# 2.net
KiCad netlist of a schematic drawn in Altium Designer
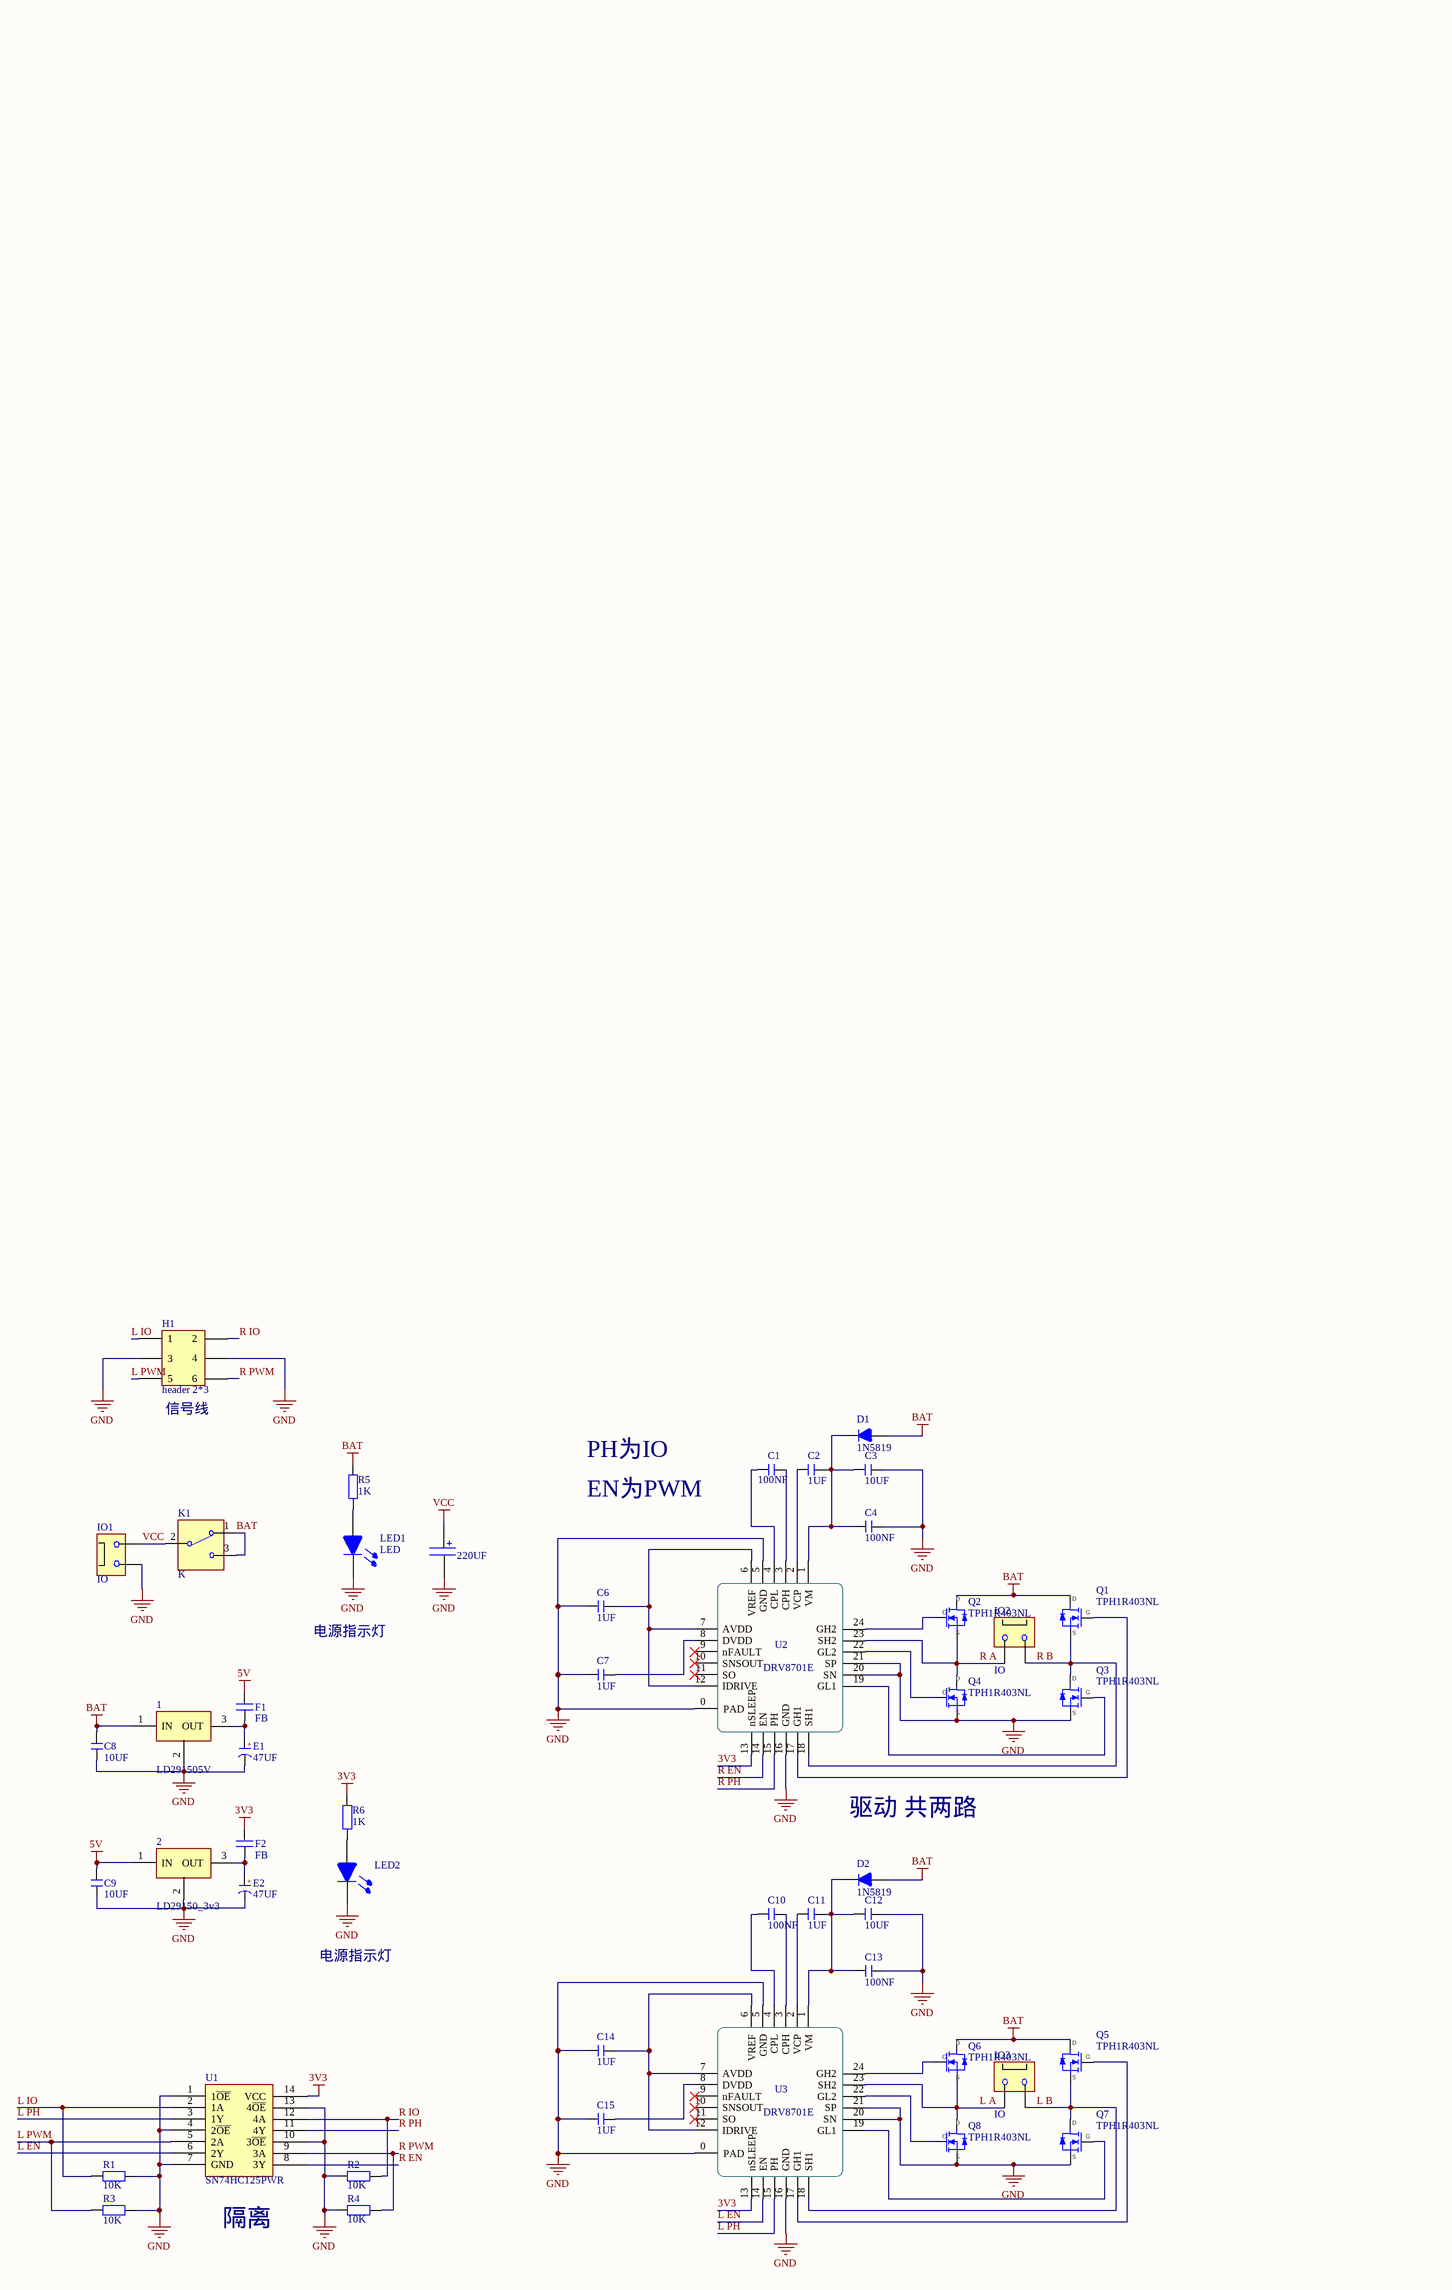
[diagram p0: 驱动2.SchDoc]

(export (version "E")
  (design (tool "Eeschema 10.0.6"))
  (components
    (comp (ref "1")
      (value "LD291505V")
      (footprint "LC-TO-252-2")
      (description "5v转压")
      (libsource (lib "驱动2") (part "LD291505V"))
    )
    (comp (ref "2")
      (value "LD29150_3v3")
      (footprint "LC-TO-252-2")
      (description "转压3v3")
      (libsource (lib "驱动2") (part "LD29150_3v3"))
    )
    (comp (ref "C1")
      (value "100NF")
      (footprint "0603-C")
      (description "无极性贴片电容")
      (fields (field (name "版权归属") "源创客"))
      (libsource (lib "驱动2") (part "C"))
    )
    (comp (ref "C2")
      (value "1UF")
      (footprint "0603-C")
      (description "无极性贴片电容")
      (fields (field (name "版权归属") "源创客"))
      (libsource (lib "驱动2") (part "C"))
    )
    (comp (ref "C3")
      (value "10UF")
      (footprint "0603-C")
      (description "无极性贴片电容")
      (fields (field (name "版权归属") "源创客"))
      (libsource (lib "驱动2") (part "C"))
    )
    (comp (ref "C4")
      (value "100NF")
      (footprint "0603-C")
      (description "无极性贴片电容")
      (fields (field (name "版权归属") "源创客"))
      (libsource (lib "驱动2") (part "C"))
    )
    (comp (ref "C5")
      (value "220UF")
      (footprint "Cap electro 6_3x12_5x2_5mm")
      (description "有极电容")
      (libsource (lib "驱动2") (part "C+"))
    )
    (comp (ref "C6")
      (value "1UF")
      (footprint "0603-C")
      (description "无极性贴片电容")
      (fields (field (name "版权归属") "源创客"))
      (libsource (lib "驱动2") (part "C"))
    )
    (comp (ref "C7")
      (value "1UF")
      (footprint "0603-C")
      (description "无极性贴片电容")
      (fields (field (name "版权归属") "源创客"))
      (libsource (lib "驱动2") (part "C"))
    )
    (comp (ref "C8")
      (value "10UF")
      (footprint "0603-C")
      (description "无极性贴片电容")
      (fields (field (name "版权归属") "源创客"))
      (libsource (lib "驱动2") (part "C"))
    )
    (comp (ref "C9")
      (value "10UF")
      (footprint "0603-C")
      (description "无极性贴片电容")
      (fields (field (name "版权归属") "源创客"))
      (libsource (lib "驱动2") (part "C"))
    )
    (comp (ref "C10")
      (value "100NF")
      (footprint "0603-C")
      (description "无极性贴片电容")
      (fields (field (name "版权归属") "源创客"))
      (libsource (lib "驱动2") (part "C"))
    )
    (comp (ref "C11")
      (value "1UF")
      (footprint "0603-C")
      (description "无极性贴片电容")
      (fields (field (name "版权归属") "源创客"))
      (libsource (lib "驱动2") (part "C"))
    )
    (comp (ref "C12")
      (value "10UF")
      (footprint "0603-C")
      (description "无极性贴片电容")
      (fields (field (name "版权归属") "源创客"))
      (libsource (lib "驱动2") (part "C"))
    )
    (comp (ref "C13")
      (value "100NF")
      (footprint "0603-C")
      (description "无极性贴片电容")
      (fields (field (name "版权归属") "源创客"))
      (libsource (lib "驱动2") (part "C"))
    )
    (comp (ref "C14")
      (value "1UF")
      (footprint "0603-C")
      (description "无极性贴片电容")
      (fields (field (name "版权归属") "源创客"))
      (libsource (lib "驱动2") (part "C"))
    )
    (comp (ref "C15")
      (value "1UF")
      (footprint "0603-C")
      (description "无极性贴片电容")
      (fields (field (name "版权归属") "源创客"))
      (libsource (lib "驱动2") (part "C"))
    )
    (comp (ref "D1")
      (value "1N5819")
      (footprint "SMA")
      (description "二极管")
      (libsource (lib "驱动2") (part "D"))
    )
    (comp (ref "D2")
      (value "1N5819")
      (footprint "SMA")
      (description "二极管")
      (libsource (lib "驱动2") (part "D"))
    )
    (comp (ref "E1")
      (value "47UF")
      (footprint "A106C钽电容")
      (description "贴片钽电容")
      (fields (field (name "版权归属") "源创客"))
      (libsource (lib "驱动2") (part "C-CD"))
    )
    (comp (ref "E2")
      (value "47UF")
      (footprint "A106C钽电容")
      (description "贴片钽电容")
      (fields (field (name "版权归属") "源创客"))
      (libsource (lib "驱动2") (part "C-CD"))
    )
    (comp (ref "F1")
      (value "FB")
      (footprint "0603-C")
      (description "0欧磁珠")
      (libsource (lib "驱动2") (part "FB"))
    )
    (comp (ref "F2")
      (value "FB")
      (footprint "0603-C")
      (description "0欧磁珠")
      (libsource (lib "驱动2") (part "FB"))
    )
    (comp (ref "H1")
      (value "header 2*3")
      (footprint "HDR2.54-LI-2x3P")
      (description "编码器，PWM")
      (libsource (lib "驱动2") (part "header 2*3"))
    )
    (comp (ref "IO1") (value "IO") (footprint "XT30") (description "接口") (libsource (lib "") (part "IO_1")))
    (comp (ref "IO2") (value "IO") (footprint "XT30") (description "接口") (libsource (lib "驱动2") (part "IO")))
    (comp (ref "IO3") (value "IO") (footprint "XT30") (description "接口") (libsource (lib "驱动2") (part "IO")))
    (comp (ref "K1")
      (value "K")
      (footprint "SW-SPDT-3A250V")
      (description "开关")
      (libsource (lib "驱动2") (part "K"))
    )
    (comp (ref "LED1") (value "LED") (footprint "0603-LED-R") (libsource (lib "驱动2") (part "LED")))
    (comp (ref "LED2") (value "LED") (footprint "0603-LED-R") (libsource (lib "驱动2") (part "LED")))
    (comp (ref "Q1")
      (value "TPH1R403NL")
      (footprint "DFN5x6")
      (description "东芝 N沟 MOS")
      (libsource (lib "逐飞集成封装库") (part "TPH1R403NL"))
    )
    (comp (ref "Q2")
      (value "TPH1R403NL")
      (footprint "DFN5x6")
      (description "东芝 N沟 MOS")
      (libsource (lib "逐飞集成封装库") (part "TPH1R403NL"))
    )
    (comp (ref "Q3")
      (value "TPH1R403NL")
      (footprint "DFN5x6")
      (description "东芝 N沟 MOS")
      (libsource (lib "逐飞集成封装库") (part "TPH1R403NL"))
    )
    (comp (ref "Q4")
      (value "TPH1R403NL")
      (footprint "DFN5x6")
      (description "东芝 N沟 MOS")
      (libsource (lib "逐飞集成封装库") (part "TPH1R403NL"))
    )
    (comp (ref "Q5")
      (value "TPH1R403NL")
      (footprint "DFN5x6")
      (description "东芝 N沟 MOS")
      (libsource (lib "逐飞集成封装库") (part "TPH1R403NL"))
    )
    (comp (ref "Q6")
      (value "TPH1R403NL")
      (footprint "DFN5x6")
      (description "东芝 N沟 MOS")
      (libsource (lib "逐飞集成封装库") (part "TPH1R403NL"))
    )
    (comp (ref "Q7")
      (value "TPH1R403NL")
      (footprint "DFN5x6")
      (description "东芝 N沟 MOS")
      (libsource (lib "逐飞集成封装库") (part "TPH1R403NL"))
    )
    (comp (ref "Q8")
      (value "TPH1R403NL")
      (footprint "DFN5x6")
      (description "东芝 N沟 MOS")
      (libsource (lib "逐飞集成封装库") (part "TPH1R403NL"))
    )
    (comp (ref "R1")
      (value "10K")
      (footprint "LC-0603_R")
      (description "1K")
      (fields (field (name "Comment") "Res2") (field (name "PUBLISHER") "Altium Limited"))
      (libsource (lib "") (part "Res2_3_2"))
    )
    (comp (ref "R2")
      (value "10K")
      (footprint "LC-0603_R")
      (description "1K")
      (fields (field (name "Comment") "Res2") (field (name "PUBLISHER") "Altium Limited"))
      (libsource (lib "") (part "Res2_3_1"))
    )
    (comp (ref "R3")
      (value "10K")
      (footprint "LC-0603_R")
      (description "1K")
      (fields (field (name "Comment") "Res2") (field (name "PUBLISHER") "Altium Limited"))
      (libsource (lib "") (part "Res2_3_1"))
    )
    (comp (ref "R4")
      (value "10K")
      (footprint "LC-0603_R")
      (description "1K")
      (fields (field (name "Comment") "Res2") (field (name "PUBLISHER") "Altium Limited"))
      (libsource (lib "") (part "Res2_3_1"))
    )
    (comp (ref "R5")
      (value "1K")
      (footprint "LC-0603_R")
      (fields (field (name "Comment") "Res2") (field (name "PUBLISHER") "Altium Limited"))
      (libsource (lib "驱动2") (part "Res2_3"))
    )
    (comp (ref "R6")
      (value "1K")
      (footprint "LC-0603_R")
      (fields (field (name "Comment") "Res2") (field (name "PUBLISHER") "Altium Limited"))
      (libsource (lib "驱动2") (part "Res2_3"))
    )
    (comp (ref "U1")
      (value "SN74HC125PWR")
      (footprint "TSSOP14")
      (fields (field (name "PUBLISHER") "Altium Limited"))
      (libsource (lib "驱动2") (part "SN74HC125PWR"))
    )
    (comp (ref "U2")
      (value "DRV8701E")
      (footprint "QFN24-4x4")
      (description "DRV8701E Ti全桥驱动芯片")
      (libsource (lib "逐飞集成封装库") (part "DRV8701E"))
    )
    (comp (ref "U3")
      (value "DRV8701E")
      (footprint "QFN24-4x4")
      (description "DRV8701E Ti全桥驱动芯片")
      (libsource (lib "逐飞集成封装库") (part "DRV8701E"))
    )
  )
  (nets
    (net (code "1") (name "/L A") (class "Default")
      (node (ref "IO3") (pin "2") (pinfunction "2_2") (pintype "passive"))
      (node (ref "Q6") (pin "3") (pinfunction "S_3") (pintype "passive"))
      (node (ref "Q8") (pin "1") (pinfunction "D_1") (pintype "passive"))
      (node (ref "U3") (pin "23") (pinfunction "SH2_23") (pintype "passive"))
    )
    (net (code "2") (name "/L B") (class "Default")
      (node (ref "IO3") (pin "1") (pinfunction "1_1") (pintype "passive"))
      (node (ref "Q5") (pin "3") (pinfunction "S_3") (pintype "passive"))
      (node (ref "Q7") (pin "1") (pinfunction "D_1") (pintype "passive"))
      (node (ref "U3") (pin "18") (pinfunction "SH1_18") (pintype "passive"))
    )
    (net (code "3") (name "/L EN") (class "Default")
      (node (ref "U1") (pin "6") (pinfunction "2Y_6") (pintype "passive"))
      (node (ref "U3") (pin "14") (pinfunction "EN_14") (pintype "passive"))
    )
    (net (code "4") (name "/L IO") (class "Default")
      (node (ref "H1") (pin "1") (pinfunction "1_1") (pintype "passive"))
      (node (ref "R1") (pin "2") (pinfunction "2_2") (pintype "passive"))
      (node (ref "U1") (pin "2") (pinfunction "1A_2") (pintype "passive"))
    )
    (net (code "5") (name "/L PH") (class "Default")
      (node (ref "U1") (pin "3") (pinfunction "1Y_3") (pintype "passive"))
      (node (ref "U3") (pin "15") (pinfunction "PH_15") (pintype "passive"))
    )
    (net (code "6") (name "/L PWM") (class "Default")
      (node (ref "H1") (pin "5") (pinfunction "5_5") (pintype "passive"))
      (node (ref "R3") (pin "1") (pinfunction "1_1") (pintype "passive"))
      (node (ref "U1") (pin "5") (pinfunction "2A_5") (pintype "passive"))
    )
    (net (code "7") (name "/R A") (class "Default")
      (node (ref "IO2") (pin "2") (pinfunction "2_2") (pintype "passive"))
      (node (ref "Q2") (pin "3") (pinfunction "S_3") (pintype "passive"))
      (node (ref "Q4") (pin "1") (pinfunction "D_1") (pintype "passive"))
      (node (ref "U2") (pin "23") (pinfunction "SH2_23") (pintype "passive"))
    )
    (net (code "8") (name "/R B") (class "Default")
      (node (ref "IO2") (pin "1") (pinfunction "1_1") (pintype "passive"))
      (node (ref "Q1") (pin "3") (pinfunction "S_3") (pintype "passive"))
      (node (ref "Q3") (pin "1") (pinfunction "D_1") (pintype "passive"))
      (node (ref "U2") (pin "18") (pinfunction "SH1_18") (pintype "passive"))
    )
    (net (code "9") (name "/R EN") (class "Default")
      (node (ref "U1") (pin "8") (pinfunction "3Y_8") (pintype "passive"))
      (node (ref "U2") (pin "14") (pinfunction "EN_14") (pintype "passive"))
    )
    (net (code "10") (name "/R IO") (class "Default")
      (node (ref "H1") (pin "2") (pinfunction "2_2") (pintype "passive"))
      (node (ref "R2") (pin "2") (pinfunction "2_2") (pintype "passive"))
      (node (ref "U1") (pin "12") (pinfunction "4A_12") (pintype "passive"))
    )
    (net (code "11") (name "/R PH") (class "Default")
      (node (ref "U1") (pin "11") (pinfunction "4Y_11") (pintype "passive"))
      (node (ref "U2") (pin "15") (pinfunction "PH_15") (pintype "passive"))
    )
    (net (code "12") (name "/R PWM") (class "Default")
      (node (ref "H1") (pin "6") (pinfunction "6_6") (pintype "passive"))
      (node (ref "R4") (pin "2") (pinfunction "2_2") (pintype "passive"))
      (node (ref "U1") (pin "9") (pinfunction "3A_9") (pintype "passive"))
    )
    (net (code "13") (name "3V3") (class "Default")
      (node (ref "F2") (pin "2") (pinfunction "2_2") (pintype "passive"))
      (node (ref "R6") (pin "1") (pinfunction "1_1") (pintype "passive"))
      (node (ref "U1") (pin "14") (pinfunction "VCC_14") (pintype "passive"))
      (node (ref "U2") (pin "13") (pinfunction "nSLEEP_13") (pintype "passive"))
      (node (ref "U3") (pin "13") (pinfunction "nSLEEP_13") (pintype "passive"))
    )
    (net (code "14") (name "5V") (class "Default")
      (node (ref "2") (pin "1") (pinfunction "IN_1") (pintype "passive"))
      (node (ref "C9") (pin "2") (pinfunction "2_2") (pintype "passive"))
      (node (ref "F1") (pin "2") (pinfunction "2_2") (pintype "passive"))
    )
    (net (code "15") (name "BAT") (class "Default")
      (node (ref "1") (pin "1") (pinfunction "IN_1") (pintype "passive"))
      (node (ref "C8") (pin "2") (pinfunction "2_2") (pintype "passive"))
      (node (ref "D1") (pin "1") (pinfunction "A_1") (pintype "passive"))
      (node (ref "D2") (pin "1") (pinfunction "A_1") (pintype "passive"))
      (node (ref "K1") (pin "1") (pinfunction "1_1") (pintype "passive"))
      (node (ref "K1") (pin "3") (pinfunction "3_3") (pintype "passive"))
      (node (ref "Q1") (pin "1") (pinfunction "D_1") (pintype "passive"))
      (node (ref "Q2") (pin "1") (pinfunction "D_1") (pintype "passive"))
      (node (ref "Q5") (pin "1") (pinfunction "D_1") (pintype "passive"))
      (node (ref "Q6") (pin "1") (pinfunction "D_1") (pintype "passive"))
      (node (ref "R5") (pin "1") (pinfunction "1_1") (pintype "passive"))
    )
    (net (code "16") (name "GND") (class "Default")
      (node (ref "1") (pin "2") (pinfunction "GND_2") (pintype "passive"))
      (node (ref "2") (pin "2") (pinfunction "GND_2") (pintype "passive"))
      (node (ref "C12") (pin "1") (pinfunction "1_1") (pintype "passive"))
      (node (ref "C13") (pin "2") (pinfunction "2_2") (pintype "passive"))
      (node (ref "C14") (pin "1") (pinfunction "1_1") (pintype "passive"))
      (node (ref "C15") (pin "1") (pinfunction "1_1") (pintype "passive"))
      (node (ref "C3") (pin "1") (pinfunction "1_1") (pintype "passive"))
      (node (ref "C4") (pin "2") (pinfunction "2_2") (pintype "passive"))
      (node (ref "C5") (pin "2") (pinfunction "2_2") (pintype "passive"))
      (node (ref "C6") (pin "1") (pinfunction "1_1") (pintype "passive"))
      (node (ref "C7") (pin "1") (pinfunction "1_1") (pintype "passive"))
      (node (ref "C8") (pin "1") (pinfunction "1_1") (pintype "passive"))
      (node (ref "C9") (pin "1") (pinfunction "1_1") (pintype "passive"))
      (node (ref "E1") (pin "2") (pinfunction "K_2") (pintype "passive"))
      (node (ref "E2") (pin "2") (pinfunction "K_2") (pintype "passive"))
      (node (ref "H1") (pin "3") (pinfunction "3_3") (pintype "passive"))
      (node (ref "H1") (pin "4") (pinfunction "4_4") (pintype "passive"))
      (node (ref "IO1") (pin "2") (pinfunction "2_2") (pintype "passive"))
      (node (ref "LED1") (pin "LED-") (pinfunction "2_LED-") (pintype "passive"))
      (node (ref "LED2") (pin "LED-") (pinfunction "2_LED-") (pintype "passive"))
      (node (ref "Q3") (pin "3") (pinfunction "S_3") (pintype "passive"))
      (node (ref "Q4") (pin "3") (pinfunction "S_3") (pintype "passive"))
      (node (ref "Q7") (pin "3") (pinfunction "S_3") (pintype "passive"))
      (node (ref "Q8") (pin "3") (pinfunction "S_3") (pintype "passive"))
      (node (ref "R1") (pin "1") (pinfunction "1_1") (pintype "passive"))
      (node (ref "R2") (pin "1") (pinfunction "1_1") (pintype "passive"))
      (node (ref "R3") (pin "2") (pinfunction "2_2") (pintype "passive"))
      (node (ref "R4") (pin "1") (pinfunction "1_1") (pintype "passive"))
      (node (ref "U1") (pin "1") (pinfunction "1~{OE}_1") (pintype "passive"))
      (node (ref "U1") (pin "10") (pinfunction "3~{OE}_10") (pintype "passive"))
      (node (ref "U1") (pin "13") (pinfunction "4~{OE}_13") (pintype "passive"))
      (node (ref "U1") (pin "4") (pinfunction "2~{OE}_4") (pintype "passive"))
      (node (ref "U1") (pin "7") (pinfunction "GND_7") (pintype "passive"))
      (node (ref "U2") (pin "0") (pinfunction "PAD_0") (pintype "passive"))
      (node (ref "U2") (pin "16") (pinfunction "GND_16") (pintype "passive"))
      (node (ref "U2") (pin "20") (pinfunction "SN_20") (pintype "passive"))
      (node (ref "U2") (pin "21") (pinfunction "SP_21") (pintype "passive"))
      (node (ref "U2") (pin "5") (pinfunction "GND_5") (pintype "passive"))
      (node (ref "U3") (pin "0") (pinfunction "PAD_0") (pintype "passive"))
      (node (ref "U3") (pin "16") (pinfunction "GND_16") (pintype "passive"))
      (node (ref "U3") (pin "20") (pinfunction "SN_20") (pintype "passive"))
      (node (ref "U3") (pin "21") (pinfunction "SP_21") (pintype "passive"))
      (node (ref "U3") (pin "5") (pinfunction "GND_5") (pintype "passive"))
    )
    (net (code "17") (name "Net-(1-OUT)") (class "Default")
      (node (ref "1") (pin "3") (pinfunction "OUT_3") (pintype "passive"))
      (node (ref "E1") (pin "1") (pinfunction "A_1") (pintype "passive"))
      (node (ref "F1") (pin "1") (pinfunction "1_1") (pintype "passive"))
    )
    (net (code "18") (name "Net-(2-OUT)") (class "Default")
      (node (ref "2") (pin "3") (pinfunction "OUT_3") (pintype "passive"))
      (node (ref "E2") (pin "1") (pinfunction "A_1") (pintype "passive"))
      (node (ref "F2") (pin "1") (pinfunction "1_1") (pintype "passive"))
    )
    (net (code "19") (name "Net-(D1-K)") (class "Default")
      (node (ref "C2") (pin "1") (pinfunction "1_1") (pintype "passive"))
      (node (ref "C3") (pin "2") (pinfunction "2_2") (pintype "passive"))
      (node (ref "C4") (pin "1") (pinfunction "1_1") (pintype "passive"))
      (node (ref "D1") (pin "2") (pinfunction "K_2") (pintype "passive"))
      (node (ref "U2") (pin "1") (pinfunction "VM_1") (pintype "passive"))
    )
    (net (code "20") (name "Net-(D2-K)") (class "Default")
      (node (ref "C11") (pin "1") (pinfunction "1_1") (pintype "passive"))
      (node (ref "C12") (pin "2") (pinfunction "2_2") (pintype "passive"))
      (node (ref "C13") (pin "1") (pinfunction "1_1") (pintype "passive"))
      (node (ref "D2") (pin "2") (pinfunction "K_2") (pintype "passive"))
      (node (ref "U3") (pin "1") (pinfunction "VM_1") (pintype "passive"))
    )
    (net (code "21") (name "Net-(LED1-1)") (class "Default")
      (node (ref "LED1") (pin "LED+") (pinfunction "1_LED+") (pintype "passive"))
      (node (ref "R5") (pin "2") (pinfunction "2_2") (pintype "passive"))
    )
    (net (code "22") (name "Net-(LED2-1)") (class "Default")
      (node (ref "LED2") (pin "LED+") (pinfunction "1_LED+") (pintype "passive"))
      (node (ref "R6") (pin "2") (pinfunction "2_2") (pintype "passive"))
    )
    (net (code "23") (name "Net-(Q1-G)") (class "Default")
      (node (ref "Q1") (pin "2") (pinfunction "G_2") (pintype "passive"))
      (node (ref "U2") (pin "17") (pinfunction "GH1_17") (pintype "passive"))
    )
    (net (code "24") (name "Net-(Q2-G)") (class "Default")
      (node (ref "Q2") (pin "2") (pinfunction "G_2") (pintype "passive"))
      (node (ref "U2") (pin "24") (pinfunction "GH2_24") (pintype "passive"))
    )
    (net (code "25") (name "Net-(Q3-G)") (class "Default")
      (node (ref "Q3") (pin "2") (pinfunction "G_2") (pintype "passive"))
      (node (ref "U2") (pin "19") (pinfunction "GL1_19") (pintype "passive"))
    )
    (net (code "26") (name "Net-(Q4-G)") (class "Default")
      (node (ref "Q4") (pin "2") (pinfunction "G_2") (pintype "passive"))
      (node (ref "U2") (pin "22") (pinfunction "GL2_22") (pintype "passive"))
    )
    (net (code "27") (name "Net-(Q5-G)") (class "Default")
      (node (ref "Q5") (pin "2") (pinfunction "G_2") (pintype "passive"))
      (node (ref "U3") (pin "17") (pinfunction "GH1_17") (pintype "passive"))
    )
    (net (code "28") (name "Net-(Q6-G)") (class "Default")
      (node (ref "Q6") (pin "2") (pinfunction "G_2") (pintype "passive"))
      (node (ref "U3") (pin "24") (pinfunction "GH2_24") (pintype "passive"))
    )
    (net (code "29") (name "Net-(Q7-G)") (class "Default")
      (node (ref "Q7") (pin "2") (pinfunction "G_2") (pintype "passive"))
      (node (ref "U3") (pin "19") (pinfunction "GL1_19") (pintype "passive"))
    )
    (net (code "30") (name "Net-(Q8-G)") (class "Default")
      (node (ref "Q8") (pin "2") (pinfunction "G_2") (pintype "passive"))
      (node (ref "U3") (pin "22") (pinfunction "GL2_22") (pintype "passive"))
    )
    (net (code "31") (name "Net-(U2-AVDD)") (class "Default")
      (node (ref "C6") (pin "2") (pinfunction "2_2") (pintype "passive"))
      (node (ref "U2") (pin "12") (pinfunction "IDRIVE_12") (pintype "passive"))
      (node (ref "U2") (pin "6") (pinfunction "VREF_6") (pintype "passive"))
      (node (ref "U2") (pin "7") (pinfunction "AVDD_7") (pintype "passive"))
    )
    (net (code "32") (name "Net-(U2-CPH)") (class "Default")
      (node (ref "C1") (pin "1") (pinfunction "1_1") (pintype "passive"))
      (node (ref "U2") (pin "3") (pinfunction "CPH_3") (pintype "passive"))
    )
    (net (code "33") (name "Net-(U2-CPL)") (class "Default")
      (node (ref "C1") (pin "2") (pinfunction "2_2") (pintype "passive"))
      (node (ref "U2") (pin "4") (pinfunction "CPL_4") (pintype "passive"))
    )
    (net (code "34") (name "Net-(U2-DVDD)") (class "Default")
      (node (ref "C7") (pin "2") (pinfunction "2_2") (pintype "passive"))
      (node (ref "U2") (pin "8") (pinfunction "DVDD_8") (pintype "passive"))
    )
    (net (code "35") (name "Net-(U2-VCP)") (class "Default")
      (node (ref "C2") (pin "2") (pinfunction "2_2") (pintype "passive"))
      (node (ref "U2") (pin "2") (pinfunction "VCP_2") (pintype "passive"))
    )
    (net (code "36") (name "Net-(U3-AVDD)") (class "Default")
      (node (ref "C14") (pin "2") (pinfunction "2_2") (pintype "passive"))
      (node (ref "U3") (pin "12") (pinfunction "IDRIVE_12") (pintype "passive"))
      (node (ref "U3") (pin "6") (pinfunction "VREF_6") (pintype "passive"))
      (node (ref "U3") (pin "7") (pinfunction "AVDD_7") (pintype "passive"))
    )
    (net (code "37") (name "Net-(U3-CPH)") (class "Default")
      (node (ref "C10") (pin "1") (pinfunction "1_1") (pintype "passive"))
      (node (ref "U3") (pin "3") (pinfunction "CPH_3") (pintype "passive"))
    )
    (net (code "38") (name "Net-(U3-CPL)") (class "Default")
      (node (ref "C10") (pin "2") (pinfunction "2_2") (pintype "passive"))
      (node (ref "U3") (pin "4") (pinfunction "CPL_4") (pintype "passive"))
    )
    (net (code "39") (name "Net-(U3-DVDD)") (class "Default")
      (node (ref "C15") (pin "2") (pinfunction "2_2") (pintype "passive"))
      (node (ref "U3") (pin "8") (pinfunction "DVDD_8") (pintype "passive"))
    )
    (net (code "40") (name "Net-(U3-VCP)") (class "Default")
      (node (ref "C11") (pin "2") (pinfunction "2_2") (pintype "passive"))
      (node (ref "U3") (pin "2") (pinfunction "VCP_2") (pintype "passive"))
    )
    (net (code "41") (name "VCC") (class "Default")
      (node (ref "C5") (pin "1") (pinfunction "1_1") (pintype "passive"))
      (node (ref "IO1") (pin "1") (pinfunction "1_1") (pintype "passive"))
      (node (ref "K1") (pin "2") (pinfunction "2_2") (pintype "passive"))
    )
    (net (code "42") (name "unconnected-(U2-SNSOUT-Pad10)") (class "Default")
      (node (ref "U2") (pin "10") (pinfunction "SNSOUT_10") (pintype "passive+no_connect"))
    )
    (net (code "43") (name "unconnected-(U2-SO-Pad11)") (class "Default")
      (node (ref "U2") (pin "11") (pinfunction "SO_11") (pintype "passive+no_connect"))
    )
    (net (code "44") (name "unconnected-(U2-nFAULT-Pad9)") (class "Default")
      (node (ref "U2") (pin "9") (pinfunction "nFAULT_9") (pintype "passive+no_connect"))
    )
    (net (code "45") (name "unconnected-(U3-SNSOUT-Pad10)") (class "Default")
      (node (ref "U3") (pin "10") (pinfunction "SNSOUT_10") (pintype "passive+no_connect"))
    )
    (net (code "46") (name "unconnected-(U3-SO-Pad11)") (class "Default")
      (node (ref "U3") (pin "11") (pinfunction "SO_11") (pintype "passive+no_connect"))
    )
    (net (code "47") (name "unconnected-(U3-nFAULT-Pad9)") (class "Default")
      (node (ref "U3") (pin "9") (pinfunction "nFAULT_9") (pintype "passive+no_connect"))
    )
  )
)
